# USB_Power.net
KiCad netlist of a schematic drawn in Altium Designer
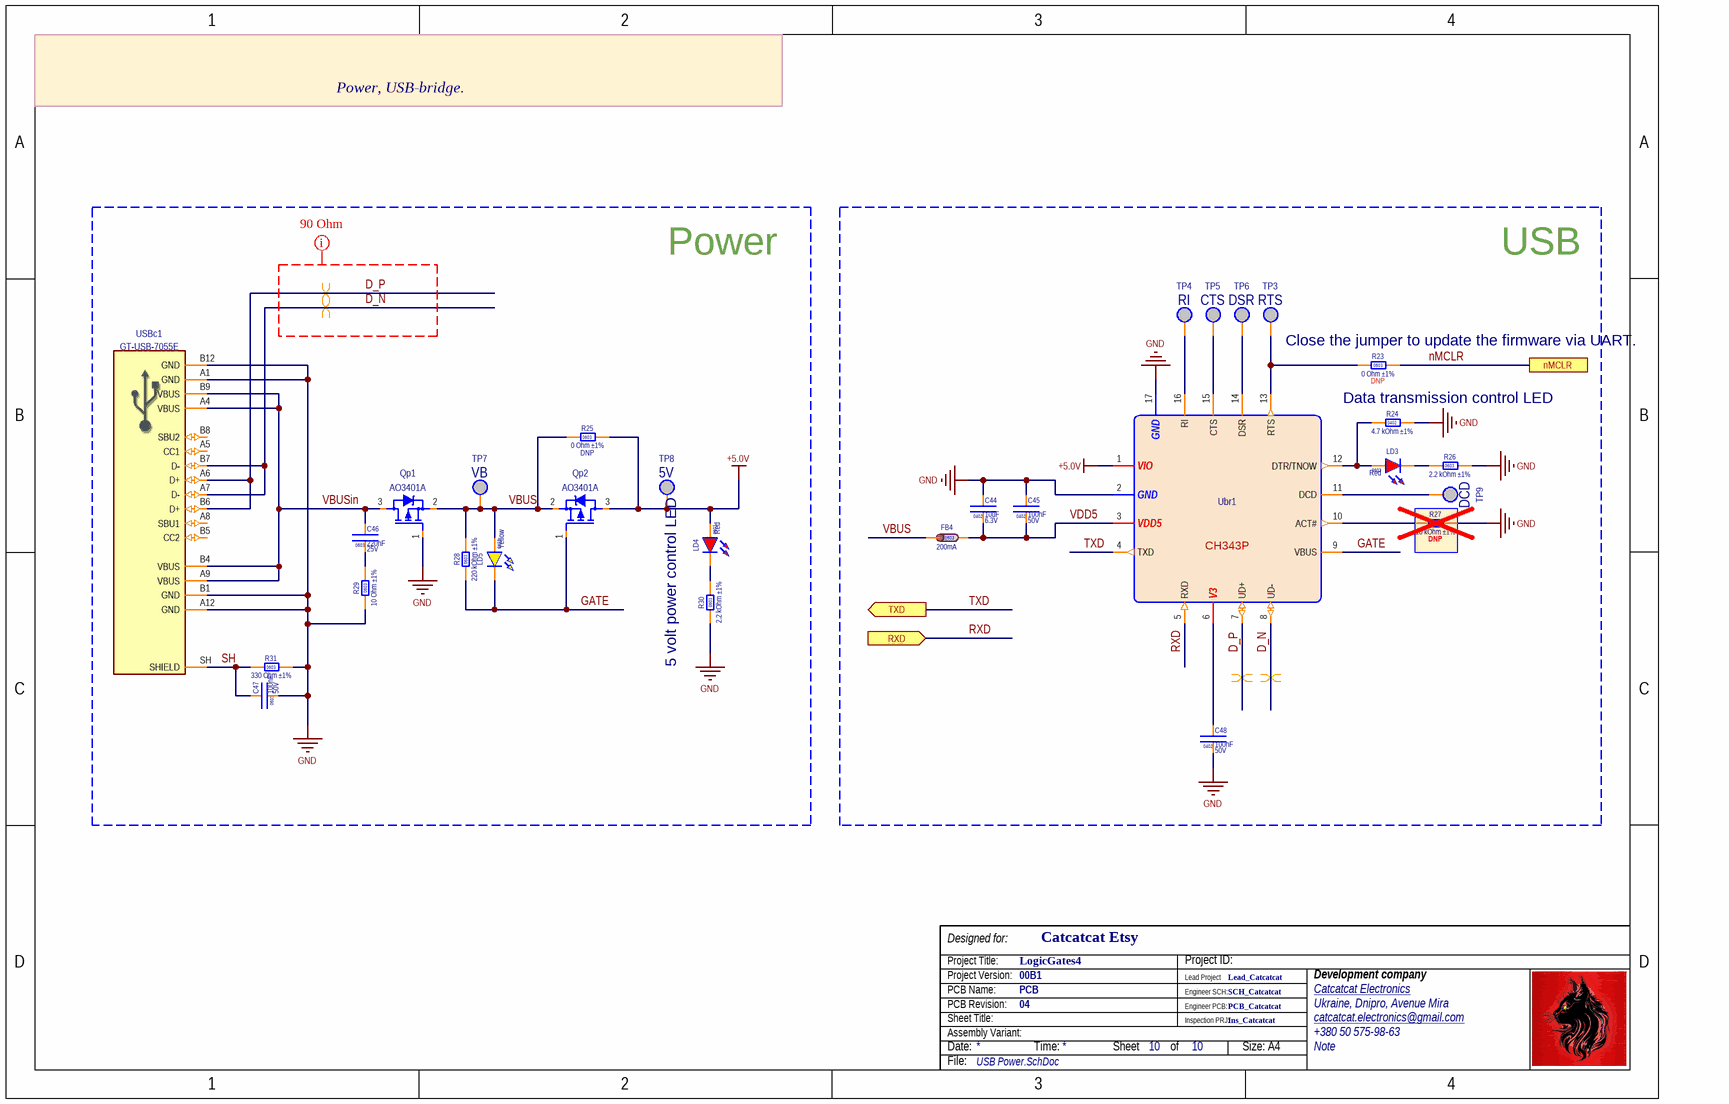
[diagram p0: USB Power.SchDoc]

(export (version "E")
  (design (tool "Eeschema 10.0.6"))
  (components
    (comp (ref "C44")
      (value "10uF")
      (footprint "CC0402(1005)x0.5")
      (description "10 uF ±10% 6.3V X7R")
      (fields
        (field (name "TOLERANCE") "±10 %")
        (field (name "VOLTAGE") "6.3V")
        (field (name "Comment") "10 uF 6.3V ±10%")
        (field (name "PUBLISHER") "Catcatcat Electronics")
      )
      (libsource (lib "IPC-7351chipCAPC") (part "0402 10 uF 6.3V (B)"))
    )
    (comp (ref "C45")
      (value "100nF")
      (footprint "CC0402(1005)x0.5")
      (description "100 nF ±10% 50V X7R")
      (fields
        (field (name "TOLERANCE") "±10 %")
        (field (name "VOLTAGE") "50V")
        (field (name "Comment") "100nF 50V ±10% 0402")
        (field (name "PUBLISHER") "Catcatcat Electronics")
      )
      (libsource (lib "IPC-7351chipCAPC") (part "0402 0.1 uF 50V (B)"))
    )
    (comp (ref "C46")
      (value "220nF")
      (footprint "CC0603(1608)x0.8")
      (description "220 nF ±10% 25V X7R")
      (fields
        (field (name "TOLERANCE") "±10%")
        (field (name "VOLTAGE") "25V")
        (field (name "Comment") "0.22 uF ±10%")
        (field (name "PUBLISHER") "Catcatcat Electronics")
      )
      (libsource (lib "IPC-7351chipCAPC") (part "0603 0.22 uF 25V (B)"))
    )
    (comp (ref "C47")
      (value "100nF")
      (footprint "CC0603(1608)x0.8")
      (description "100 nF ±10% 50V X7R")
      (fields
        (field (name "TOLERANCE") "±10%")
        (field (name "VOLTAGE") "50V")
        (field (name "Comment") "100 nF ±10% 50V")
        (field (name "PUBLISHER") "Catcatcat Electronics")
      )
      (libsource (lib "IPC-7351chipCAPC") (part "0603 0.1 uF (B)"))
    )
    (comp (ref "C48")
      (value "100nF")
      (footprint "CC0402(1005)x0.5")
      (description "100 nF ±10% 50V X7R")
      (fields
        (field (name "TOLERANCE") "±10 %")
        (field (name "VOLTAGE") "50V")
        (field (name "Comment") "100nF 50V ±10% 0402")
        (field (name "PUBLISHER") "Catcatcat Electronics")
      )
      (libsource (lib "IPC-7351chipCAPC") (part "0402 0.1 uF 50V (B)"))
    )
    (comp (ref "FB4")
      (value "200mA")
      (footprint "FB0603(1608)")
      (description "0.20A 600 Ohm @100MHz 450 mOhm")
      (fields (field (name "Comment") "GZ1608D601TF") (field (name "PUBLISHER") "Catcatcat Electronics"))
      (libsource (lib "IPC-7351chipFEB") (part "0603 GZ1608D601TF (B)"))
    )
    (comp (ref "LD3")
      (value "Red")
      (footprint "LD0603 RED")
      (description "0603 Red 520~625NM 90~100MCD@20MA Top View RoHS")
      (fields
        (field (name "CASE/PACKAGE") "0603")
        (field (name "Comment") "KT-0603R")
        (field (name "PUBLISHER") "Catcatcat Electronics")
      )
      (libsource (lib "Led") (part "KT-0603R (B)"))
    )
    (comp (ref "LD4")
      (value "Red")
      (footprint "LD0603 RED")
      (description "0603 Red 520~625NM 90~100MCD@20MA Top View RoHS")
      (fields
        (field (name "CASE/PACKAGE") "0603")
        (field (name "Comment") "KT-0603R")
        (field (name "PUBLISHER") "Catcatcat Electronics")
      )
      (libsource (lib "Led") (part "KT-0603R (B)"))
    )
    (comp (ref "LD5")
      (value "Yellow")
      (footprint "LD0603 YELLOW")
      (fields
        (field (name "CASE/PACKAGE") "0603")
        (field (name "Comment") "LED 0603 Yellow 120° 60mW")
        (field (name "PUBLISHER") "Catcatcat Electronics")
      )
      (libsource (lib "Led") (part "19-213/Y2C-CQ2R2L/3T(CY) (B)"))
    )
    (comp (ref "Qp1")
      (value "AO3401A")
      (footprint "FP-SOT23-IPC_C")
      (description "P-Channel SOT-23-3L 30V 4A 44mΩ@10V,4.3A 1.4W 1.3V@250uAl SOT-23-3L  MOSFETs ROHS")
      (fields (field (name "VOLTAGE") "30V 4A") (field (name "PUBLISHER") "Catcatcat Electronics"))
      (libsource (lib "Transistors") (part "AO3401A (B)"))
    )
    (comp (ref "Qp2")
      (value "AO3401A")
      (footprint "FP-SOT23-IPC_C")
      (description "P-Channel SOT-23-3L 30V 4A 44mΩ@10V,4.3A 1.4W 1.3V@250uAl SOT-23-3L  MOSFETs ROHS")
      (fields (field (name "VOLTAGE") "30V 4A") (field (name "PUBLISHER") "Catcatcat Electronics"))
      (libsource (lib "") (part "AO3401A (B)_1"))
    )
    (comp (ref "R23")
      (value "0 Ohm ±1%")
      (footprint "RC0603(1608)A J")
      (description "0 R (000) ±5% 1/10W 50V")
      (fields
        (field (name "TOLERANCE") "±1%")
        (field (name "VOLTAGE") "50V")
        (field (name "ASSEMBLY TYPE") "DNP")
        (field (name "PUBLISHER") "Catcatcat Electronics")
      )
      (libsource (lib "IPC-7351chipRESC") (part "0603 0 Ohm ±1% (B)"))
    )
    (comp (ref "R24")
      (value "4.7 kOhm ±1%")
      (footprint "RC0402(1005)-1%")
      (description "4.7 k (4701)±1% 1/16W 50V")
      (fields
        (field (name "TOLERANCE") "±1%")
        (field (name "VOLTAGE") "50V")
        (field (name "PUBLISHER") "Catcatcat Electronics")
      )
      (libsource (lib "IPC-7351chipRESC") (part "0402 4.7 kOhm ±1% (B)"))
    )
    (comp (ref "R25")
      (value "0 Ohm ±1%")
      (footprint "RC0603(1608)A J")
      (description "0 R (000) ±5% 1/10W 50V")
      (fields
        (field (name "TOLERANCE") "±1%")
        (field (name "VOLTAGE") "50V")
        (field (name "ASSEMBLY TYPE") "DNP")
        (field (name "PUBLISHER") "Catcatcat Electronics")
      )
      (libsource (lib "IPC-7351chipRESC") (part "0603 0 Ohm ±1% (B)"))
    )
    (comp (ref "R26")
      (value "2.2 kOhm ±1%")
      (footprint "RC0603(1608) -1%")
      (description "2.2 k (222) ±1% 1/10W 50V")
      (fields
        (field (name "TOLERANCE") "±1%")
        (field (name "VOLTAGE") "50V")
        (field (name "PUBLISHER") "Catcatcat Electronics")
      )
      (libsource (lib "IPC-7351chipRESC") (part "0603 2.2 kOhm ±1% (B)"))
    )
    (comp (ref "R27")
      (value "10 kOhm ±1%")
      (footprint "RC0402(1005)-1%")
      (description "10 k ±1% 1/16W 50V")
      (fields
        (field (name "TOLERANCE") "±1%")
        (field (name "VOLTAGE") "50V")
        (field (name "ASSEMBLY TYPE") "DNP")
        (field (name "PUBLISHER") "Catcatcat Electronics")
      )
      (libsource (lib "IPC-7351chipRESC") (part "0402 10 kOhm ±1% (B)"))
    )
    (comp (ref "R28")
      (value "220 kOhm ±1%")
      (footprint "RC0603(1608) -1%")
      (description "220 k (224) ±5% 1/10W 50V")
      (fields
        (field (name "TOLERANCE") "±1%")
        (field (name "VOLTAGE") "50V")
        (field (name "PUBLISHER") "Catcatcat Electronics")
      )
      (libsource (lib "IPC-7351chipRESC") (part "0603 220 kOhm ±1% (B)"))
    )
    (comp (ref "R29")
      (value "10 Ohm ±1%")
      (footprint "RC0603(1608) -1%")
      (description "10 R (XIO) ±1% 1/10W 50V ±400ppm/°C")
      (fields
        (field (name "TOLERANCE") "±1%")
        (field (name "VOLTAGE") "50V")
        (field (name "PUBLISHER") "Catcatcat Electronics")
      )
      (libsource (lib "IPC-7351chipRESC") (part "0603 10 Ohm ±1% (B)"))
    )
    (comp (ref "R30")
      (value "2.2 kOhm ±1%")
      (footprint "RC0603(1608) -1%")
      (description "2.2 k (222) ±1% 1/10W 50V")
      (fields
        (field (name "TOLERANCE") "±1%")
        (field (name "VOLTAGE") "50V")
        (field (name "PUBLISHER") "Catcatcat Electronics")
      )
      (libsource (lib "IPC-7351chipRESC") (part "0603 2.2 kOhm ±1% (B)"))
    )
    (comp (ref "R31")
      (value "330 Ohm ±1%")
      (footprint "RC0603(1608) -1%")
      (description "330 R (331) ±5% 1/10W 50V")
      (fields
        (field (name "TOLERANCE") "±1%")
        (field (name "VOLTAGE") "50V")
        (field (name "PUBLISHER") "Catcatcat Electronics")
      )
      (libsource (lib "IPC-7351chipRESC") (part "0603 330 Ohm ±1% (B)"))
    )
    (comp (ref "TP3")
      (value "RTS")
      (footprint "Test_Point_T_0.6mm")
      (description "Test Point TOP")
      (fields (field (name "PUBLISHER") "Catcatcat Electronics"))
      (libsource (lib "Assembly") (part "Test_Point smd_0.6"))
    )
    (comp (ref "TP4")
      (value "RI")
      (footprint "Test_Point_T_0.6mm")
      (description "Test Point TOP")
      (fields (field (name "PUBLISHER") "Catcatcat Electronics"))
      (libsource (lib "Assembly") (part "Test_Point smd_0.6"))
    )
    (comp (ref "TP5")
      (value "CTS")
      (footprint "Test_Point_T_0.6mm")
      (description "Test Point TOP")
      (fields (field (name "PUBLISHER") "Catcatcat Electronics"))
      (libsource (lib "Assembly") (part "Test_Point smd_0.6"))
    )
    (comp (ref "TP6")
      (value "DSR")
      (footprint "Test_Point_T_0.6mm")
      (description "Test Point TOP")
      (fields (field (name "PUBLISHER") "Catcatcat Electronics"))
      (libsource (lib "Assembly") (part "Test_Point smd_0.6"))
    )
    (comp (ref "TP7")
      (value "VB")
      (footprint "Test_Point_T_0.6mm")
      (description "Test Point TOP")
      (fields (field (name "PUBLISHER") "Catcatcat Electronics"))
      (libsource (lib "Assembly") (part "Test_Point smd_0.6"))
    )
    (comp (ref "TP8")
      (value "5V")
      (footprint "Test_Point_T_0.6mm")
      (description "Test Point TOP")
      (fields (field (name "PUBLISHER") "Catcatcat Electronics"))
      (libsource (lib "Assembly") (part "Test_Point smd_0.6"))
    )
    (comp (ref "TP9")
      (value "DCD")
      (footprint "Test_Point_T_0.6mm")
      (description "Test Point TOP")
      (fields (field (name "PUBLISHER") "Catcatcat Electronics"))
      (libsource (lib "Assembly") (part "Test_Point smd_0.6"))
    )
    (comp (ref "Ubr1")
      (value "CH343P")
      (footprint "TQFN-16-JLC")
      (description "USB Bridge, USB 2.0 Transceiver 2Mbps TQFN-16-EP(3x3)")
      (fields (field (name "PUBLISHER") "Catcatcat Electronics"))
      (libsource (lib "logic_chip") (part "CH343P (E)"))
    )
    (comp (ref "USBc1")
      (value "GT-USB-7055E")
      (footprint "TYPE-C16PIN-C7450622")
      (fields (field (name "PUBLISHER") "Catcatcat Electronics"))
      (libsource (lib "Connector_Interface") (part "GT-USB-7055E (E)"))
    )
  )
  (nets
    (net (code "1") (name "+5.0V") (class "Default")
      (node (ref "LD4") (pin "2") (pintype "passive"))
      (node (ref "Qp2") (pin "3") (pinfunction "D_3") (pintype "passive"))
      (node (ref "R25") (pin "2") (pintype "passive"))
      (node (ref "TP8") (pin "1") (pintype "passive"))
      (node (ref "Ubr1") (pin "1") (pinfunction "VIO_1") (pintype "passive"))
    )
    (net (code "2") (name "/D_N") (class "Default")
      (node (ref "USBc1") (pin "A7") (pinfunction "D-_A7") (pintype "bidirectional"))
      (node (ref "USBc1") (pin "B7") (pinfunction "D-_B7") (pintype "bidirectional"))
      (node (ref "Ubr1") (pin "8") (pinfunction "UD-_8") (pintype "bidirectional"))
    )
    (net (code "3") (name "/D_P") (class "Default")
      (node (ref "USBc1") (pin "A6") (pinfunction "D+_A6") (pintype "bidirectional"))
      (node (ref "USBc1") (pin "B6") (pinfunction "D+_B6") (pintype "bidirectional"))
      (node (ref "Ubr1") (pin "7") (pinfunction "UD+_7") (pintype "bidirectional"))
    )
    (net (code "4") (name "/GATE") (class "Default")
      (node (ref "LD5") (pin "1") (pintype "passive"))
      (node (ref "Qp2") (pin "1") (pinfunction "G_1") (pintype "passive"))
      (node (ref "R28") (pin "1") (pintype "passive"))
      (node (ref "Ubr1") (pin "9") (pinfunction "VBUS_9") (pintype "passive"))
    )
    (net (code "5") (name "/RXD") (class "Default")
      (node (ref "Ubr1") (pin "5") (pinfunction "RXD_5") (pintype "input"))
    )
    (net (code "6") (name "/SH") (class "Default")
      (node (ref "C47") (pin "2") (pintype "passive"))
      (node (ref "R31") (pin "1") (pintype "passive"))
      (node (ref "USBc1") (pin "SH") (pinfunction "SHIELD_SH") (pintype "power_in"))
    )
    (net (code "7") (name "/TXD") (class "Default")
      (node (ref "Ubr1") (pin "4") (pinfunction "TXD_4") (pintype "output"))
    )
    (net (code "8") (name "/VBUS") (class "Default")
      (node (ref "FB4") (pin "1") (pintype "passive"))
      (node (ref "LD5") (pin "2") (pintype "passive"))
      (node (ref "Qp1") (pin "2") (pinfunction "S_2") (pintype "passive"))
      (node (ref "Qp2") (pin "2") (pinfunction "S_2") (pintype "passive"))
      (node (ref "R25") (pin "1") (pintype "passive"))
      (node (ref "R28") (pin "2") (pintype "passive"))
      (node (ref "TP7") (pin "1") (pintype "passive"))
    )
    (net (code "9") (name "/VBUSin") (class "Default")
      (node (ref "C46") (pin "2") (pintype "passive"))
      (node (ref "Qp1") (pin "3") (pinfunction "D_3") (pintype "passive"))
      (node (ref "USBc1") (pin "A4") (pinfunction "VBUS_A4") (pintype "power_in"))
      (node (ref "USBc1") (pin "A9") (pinfunction "VBUS_A9") (pintype "passive"))
      (node (ref "USBc1") (pin "B4") (pinfunction "VBUS_B4") (pintype "passive"))
      (node (ref "USBc1") (pin "B9") (pinfunction "VBUS_B9") (pintype "power_in"))
    )
    (net (code "10") (name "/VDD5") (class "Default")
      (node (ref "C44") (pin "1") (pintype "passive"))
      (node (ref "C45") (pin "1") (pintype "passive"))
      (node (ref "FB4") (pin "2") (pintype "passive"))
      (node (ref "Ubr1") (pin "3") (pinfunction "VDD5_3") (pintype "passive"))
    )
    (net (code "11") (name "/nMCLR") (class "Default") (node (ref "R23") (pin "2") (pintype "passive")))
    (net (code "12") (name "GND") (class "Default")
      (node (ref "C44") (pin "2") (pintype "passive"))
      (node (ref "C45") (pin "2") (pintype "passive"))
      (node (ref "C47") (pin "1") (pintype "passive"))
      (node (ref "C48") (pin "1") (pintype "passive"))
      (node (ref "Qp1") (pin "1") (pinfunction "G_1") (pintype "passive"))
      (node (ref "R24") (pin "2") (pintype "passive"))
      (node (ref "R26") (pin "1") (pintype "passive"))
      (node (ref "R27") (pin "2") (pintype "passive"))
      (node (ref "R29") (pin "1") (pintype "passive"))
      (node (ref "R30") (pin "1") (pintype "passive"))
      (node (ref "R31") (pin "2") (pintype "passive"))
      (node (ref "USBc1") (pin "A1") (pinfunction "GND_A1") (pintype "power_in"))
      (node (ref "USBc1") (pin "A12") (pinfunction "GND_A12") (pintype "passive"))
      (node (ref "USBc1") (pin "B1") (pinfunction "GND_B1") (pintype "passive"))
      (node (ref "USBc1") (pin "B12") (pinfunction "GND_B12") (pintype "power_in"))
      (node (ref "Ubr1") (pin "17") (pinfunction "GND_17") (pintype "passive"))
      (node (ref "Ubr1") (pin "2") (pinfunction "GND_2") (pintype "passive"))
    )
    (net (code "13") (name "Net-(C46-Pad1)") (class "Default")
      (node (ref "C46") (pin "1") (pintype "passive"))
      (node (ref "R29") (pin "2") (pintype "passive"))
    )
    (net (code "14") (name "Net-(LD3-Pad1)") (class "Default")
      (node (ref "LD3") (pin "1") (pintype "passive"))
      (node (ref "R26") (pin "2") (pintype "passive"))
    )
    (net (code "15") (name "Net-(LD4-Pad1)") (class "Default")
      (node (ref "LD4") (pin "1") (pintype "passive"))
      (node (ref "R30") (pin "2") (pintype "passive"))
    )
    (net (code "16") (name "Net-(Ubr1-ACT#)") (class "Default")
      (node (ref "R27") (pin "1") (pintype "passive"))
      (node (ref "Ubr1") (pin "10") (pinfunction "ACT#_10") (pintype "output"))
    )
    (net (code "17") (name "Net-(Ubr1-CTS)") (class "Default")
      (node (ref "TP5") (pin "1") (pintype "passive"))
      (node (ref "Ubr1") (pin "15") (pinfunction "CTS_15") (pintype "passive"))
    )
    (net (code "18") (name "Net-(Ubr1-DCD)") (class "Default")
      (node (ref "TP9") (pin "1") (pintype "passive"))
      (node (ref "Ubr1") (pin "11") (pinfunction "DCD_11") (pintype "passive"))
    )
    (net (code "19") (name "Net-(Ubr1-DSR)") (class "Default")
      (node (ref "TP6") (pin "1") (pintype "passive"))
      (node (ref "Ubr1") (pin "14") (pinfunction "DSR_14") (pintype "passive"))
    )
    (net (code "20") (name "Net-(Ubr1-DTR{slash}TNOW)") (class "Default")
      (node (ref "LD3") (pin "2") (pintype "passive"))
      (node (ref "R24") (pin "1") (pintype "passive"))
      (node (ref "Ubr1") (pin "12") (pinfunction "DTR/TNOW_12") (pintype "output"))
    )
    (net (code "21") (name "Net-(Ubr1-RI)") (class "Default")
      (node (ref "TP4") (pin "1") (pintype "passive"))
      (node (ref "Ubr1") (pin "16") (pinfunction "RI_16") (pintype "passive"))
    )
    (net (code "22") (name "Net-(Ubr1-RTS)") (class "Default")
      (node (ref "R23") (pin "1") (pintype "passive"))
      (node (ref "TP3") (pin "1") (pintype "passive"))
      (node (ref "Ubr1") (pin "13") (pinfunction "RTS_13") (pintype "output"))
    )
    (net (code "23") (name "Net-(Ubr1-V3)") (class "Default")
      (node (ref "C48") (pin "2") (pintype "passive"))
      (node (ref "Ubr1") (pin "6") (pinfunction "V3_6") (pintype "passive"))
    )
    (net (code "24") (name "unconnected-(USBc1-CC1-PadA5)") (class "Default")
      (node (ref "USBc1") (pin "A5") (pinfunction "CC1_A5") (pintype "bidirectional"))
    )
    (net (code "25") (name "unconnected-(USBc1-CC2-PadB5)") (class "Default")
      (node (ref "USBc1") (pin "B5") (pinfunction "CC2_B5") (pintype "bidirectional"))
    )
    (net (code "26") (name "unconnected-(USBc1-SBU1-PadA8)") (class "Default")
      (node (ref "USBc1") (pin "A8") (pinfunction "SBU1_A8") (pintype "bidirectional"))
    )
    (net (code "27") (name "unconnected-(USBc1-SBU2-PadB8)") (class "Default")
      (node (ref "USBc1") (pin "B8") (pinfunction "SBU2_B8") (pintype "bidirectional"))
    )
  )
)
